# PCB_Schematic_Sheet_2.net
KiCad netlist of a schematic drawn in Altium Designer
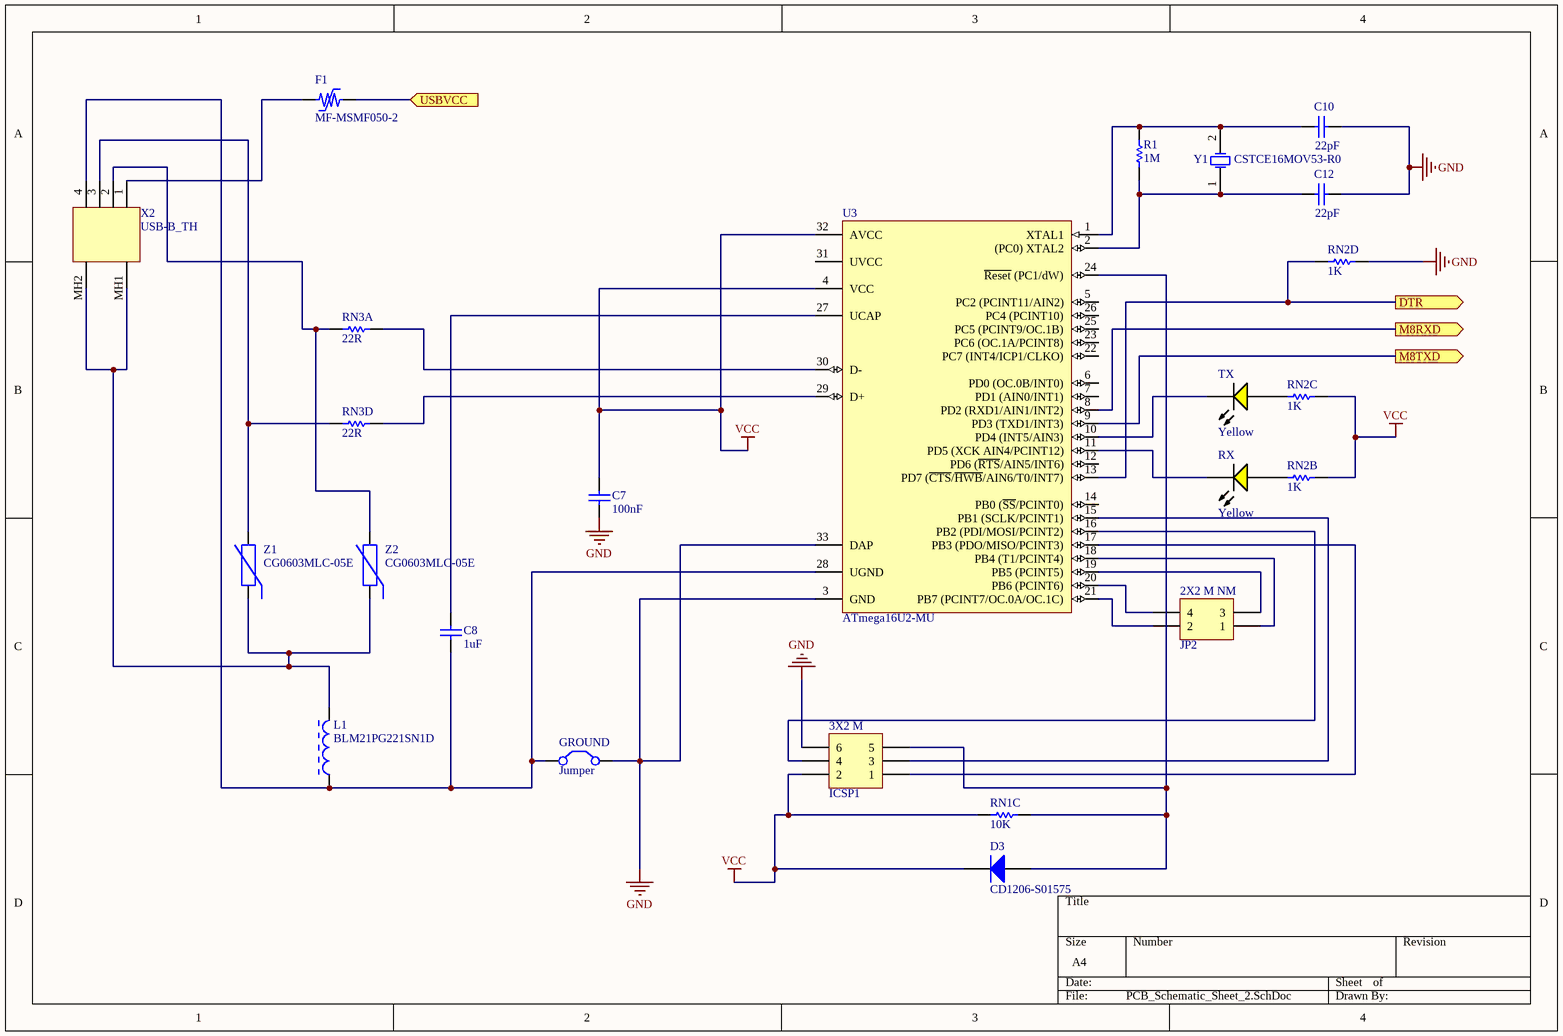
[diagram p0: PCB_Schematic_Sheet_2.SchDoc]

(export (version "E")
  (design (tool "Eeschema 10.0.6"))
  (components
    (comp (ref "2X2 M NM")
      (value "JP2")
      (footprint "HDR2X2")
      (description "Header, 2-Pin, Dual row")
      (fields (field (name "PUBLISHER") "Altium Limited"))
      (libsource (lib "Miscellaneous Connectors") (part "Header 2X2"))
    )
    (comp (ref "3X2 M")
      (value "ICSP1")
      (footprint "HDR2X3")
      (description "Header, 3-Pin, Dual row")
      (fields (field (name "PUBLISHER") "Altium Limited"))
      (libsource (lib "Miscellaneous Connectors") (part "Header 3X2"))
    )
    (comp (ref "C7")
      (value "100nF")
      (footprint "CAPC0805(2012)100_M")
      (description "CAP 100nF 50V ±10% 0805 (2012 Metric) Thickness 1mm SMD")
      (fields (field (name "TOLERANCE") "Â±10%"))
      (libsource (lib "Altium Content Vault") (part "CAP"))
    )
    (comp (ref "C8")
      (value "1uF")
      (footprint "CAPC0805(2012)145_L")
      (description "CAP 1uF 50V ±10% 0805 (2012 Metric) Thickness 1.45mm SMD")
      (fields (field (name "TOLERANCE") "Â±10%"))
      (libsource (lib "Altium Content Vault") (part "CAP"))
    )
    (comp (ref "C10")
      (value "22pF")
      (footprint "CAPC0805(2012)100_M")
      (description "CAP 22pF 50V ±5% 0805 (2012 Metric) Thickness 1mm SMD")
      (fields (field (name "TOLERANCE") "Â±5%"))
      (libsource (lib "Altium Content Vault") (part "CAP"))
    )
    (comp (ref "C12")
      (value "22pF")
      (footprint "CAPC0805(2012)100_M")
      (description "CAP 22pF 50V ±5% 0805 (2012 Metric) Thickness 1mm SMD")
      (fields (field (name "TOLERANCE") "Â±5%"))
      (libsource (lib "Altium Content Vault") (part "CAP"))
    )
    (comp (ref "D3")
      (value "CD1206-S01575")
      (footprint "BOUR-CD1206-S01575-2_L")
      (description "75 V Small Signal Switching Diode, 150 mA, 2.5 uA, 1026 Molded Package, RoHS, Tape and Reel")
      (fields (field (name "MANUFACTURER") "Bourns"))
      (libsource (lib "Altium Content Vault") (part "BOUR-A1K2-2"))
    )
    (comp (ref "F1")
      (value "MF-MSMF050-2")
      (footprint "BOUR-MF-MSMF050-2_V")
      (description "PTC Resettable Fuse, 15 V, 500 mA, -40 to 85 degC, 2-Pin SMD, RoHS, Tape and Reel")
      (fields (field (name "MANUFACTURER") "Bourns"))
      (libsource (lib "Altium Content Vault") (part "PPTC-2"))
    )
    (comp (ref "GROUND")
      (value "Jumper")
      (footprint "RAD-0.2")
      (description "Jumper Wire")
      (fields (field (name "PUBLISHER") "Altium Limited"))
      (libsource (lib "Miscellaneous Devices") (part "Jumper"))
    )
    (comp (ref "L1")
      (value "BLM21PG221SN1D")
      (footprint "MURA-BLM21-B20-CHIP-2_V2")
      (fields (field (name "MANUFACTURER") "Murata"))
      (libsource (lib "Altium Content Vault") (part "MURA-FB-2"))
    )
    (comp (ref "R1")
      (value "1M")
      (footprint "RESC0805(2012)_N")
      (description "1M 0.125W 1% 0805 (2012 Metric)  SMD")
      (fields (field (name "POWER") "0.125 W") (field (name "TOLERANCE") "1 %"))
      (libsource (lib "Altium Content Vault") (part "RES"))
    )
    (comp (ref "RN1C")
      (value "10K")
      (footprint "RESC0805(2012)_M")
      (description "10K 0.125W 1% 0805 (2012 Metric)  SMD")
      (fields (field (name "TOLERANCE") "1 %") (field (name "POWER") "0.125 W"))
      (libsource (lib "Altium Content Vault") (part "RES"))
    )
    (comp (ref "RN2B")
      (value "1K")
      (footprint "RESC0805(2012)_N")
      (description "1K 0.125W 5% 0805 (2012 Metric)  SMD")
      (fields (field (name "POWER") "0.125 W") (field (name "TOLERANCE") "5 %"))
      (libsource (lib "Altium Content Vault") (part "RES"))
    )
    (comp (ref "RN2C")
      (value "1K")
      (footprint "RESC0805(2012)_N")
      (description "1K 0.125W 5% 0805 (2012 Metric)  SMD")
      (fields (field (name "POWER") "0.125 W") (field (name "TOLERANCE") "5 %"))
      (libsource (lib "Altium Content Vault") (part "RES"))
    )
    (comp (ref "RN2D")
      (value "1K")
      (footprint "RESC0805(2012)_N")
      (description "1K 0.125W 5% 0805 (2012 Metric)  SMD")
      (fields (field (name "POWER") "0.125 W") (field (name "TOLERANCE") "5 %"))
      (libsource (lib "Altium Content Vault") (part "RES"))
    )
    (comp (ref "RN3A")
      (value "22R")
      (footprint "RESC0805(2012)_M")
      (description "22R 0.125W 5% 0805 (2012 Metric)  SMD")
      (fields (field (name "POWER") "0.125 W") (field (name "TOLERANCE") "5 %"))
      (libsource (lib "Altium Content Vault") (part "RES"))
    )
    (comp (ref "RN3D")
      (value "22R")
      (footprint "RESC0805(2012)_M")
      (description "22R 0.125W 5% 0805 (2012 Metric)  SMD")
      (fields (field (name "POWER") "0.125 W") (field (name "TOLERANCE") "5 %"))
      (libsource (lib "Altium Content Vault") (part "RES"))
    )
    (comp (ref "RX")
      (value "Yellow")
      (footprint "LTST-C190KSKT_V")
      (description "LED Uni-Color Yellow, 75 mW, 30 mA, -30 to 85 degC, 2-Pin SMD, RoHS, Tape and Reel")
      (fields (field (name "TOLERANCE") "1%"))
      (libsource (lib "Altium Content Vault") (part "LED-YELLOW-AK-2"))
    )
    (comp (ref "TX")
      (value "Yellow")
      (footprint "LTST-C190KSKT_V")
      (description "LED Uni-Color Yellow, 75 mW, 30 mA, -30 to 85 degC, 2-Pin SMD, RoHS, Tape and Reel")
      (fields (field (name "TOLERANCE") "1%"))
      (libsource (lib "Altium Content Vault") (part "LED-YELLOW-AK-2"))
    )
    (comp (ref "U3")
      (value "ATmega16U2-MU")
      (footprint "32PG_N")
      (libsource (lib "Altium Content Vault") (part "MC-8B-ATM8U2-SQ33"))
    )
    (comp (ref "X2")
      (value "USB-B_TH")
      (footprint "FCI-61729-0010BLF-6_V")
      (description "Single USB 2.0, B Type, Right Angle Jack, Through Hole, RoHS, Tube")
      (fields (field (name "MANUFACTURER") "FCI Electronics") (field (name "PARTNUMBER") "61729-0010BLF"))
      (libsource (lib "Altium Content Vault") (part "FCI-CN-1F-R6"))
    )
    (comp (ref "Y1")
      (value "CSTCE16MOV53-R0")
      (footprint "R38")
      (description "Crystal Oscillator")
      (fields (field (name "PUBLISHER") "Altium Limited"))
      (libsource (lib "Miscellaneous Devices") (part "XTAL"))
    )
    (comp (ref "Z1")
      (value "CG0603MLC-05E")
      (footprint "BOUR-CG0603-2_V")
      (description "ESD Protector, 5 V Supply, -40 to 85 degC, 1.6 x 0.8 x 0.55 mm SMD, RoHS, Tape and Reel")
      (fields (field (name "MANUFACTURER") "Bourns"))
      (libsource (lib "Altium Content Vault") (part "BOUR-VSR-2"))
    )
    (comp (ref "Z2")
      (value "CG0603MLC-05E")
      (footprint "BOUR-CG0603-2_V")
      (description "ESD Protector, 5 V Supply, -40 to 85 degC, 1.6 x 0.8 x 0.55 mm SMD, RoHS, Tape and Reel")
      (fields (field (name "MANUFACTURER") "Bourns"))
      (libsource (lib "Altium Content Vault") (part "BOUR-VSR-2"))
    )
  )
  (nets
    (net (code "1") (name "/DTR") (class "Default")
      (node (ref "RN2D") (pin "1") (pinfunction "1_1") (pintype "passive"))
      (node (ref "U3") (pin "13") (pinfunction "PD7_(~{CTS}/~{HWB}/AIN6/T0/INT7)_13") (pintype "bidirectional"))
    )
    (net (code "2") (name "/M8RXD") (class "Default")
      (node (ref "U3") (pin "8") (pinfunction "PD2_(RXD1/AIN1/INT2)_8") (pintype "bidirectional"))
    )
    (net (code "3") (name "/M8TXD") (class "Default")
      (node (ref "U3") (pin "9") (pinfunction "PD3_(TXD1/INT3)_9") (pintype "bidirectional"))
    )
    (net (code "4") (name "/USBVCC") (class "Default")
      (node (ref "F1") (pin "2") (pinfunction "2_2") (pintype "passive"))
    )
    (net (code "5") (name "GND") (class "Default")
      (node (ref "3X2 M") (pin "6") (pinfunction "6_6") (pintype "passive"))
      (node (ref "C10") (pin "2") (pinfunction "2_2") (pintype "passive"))
      (node (ref "C12") (pin "2") (pinfunction "2_2") (pintype "passive"))
      (node (ref "C7") (pin "1") (pinfunction "1_1") (pintype "passive"))
      (node (ref "GROUND") (pin "2") (pinfunction "C2_2") (pintype "passive"))
      (node (ref "RN2D") (pin "2") (pinfunction "2_2") (pintype "passive"))
      (node (ref "U3") (pin "3") (pinfunction "GND_3") (pintype "power_in"))
      (node (ref "U3") (pin "33") (pinfunction "DAP_33") (pintype "power_in"))
    )
    (net (code "6") (name "Net-(D3-A)") (class "Default")
      (node (ref "3X2 M") (pin "5") (pinfunction "5_5") (pintype "passive"))
      (node (ref "D3") (pin "1") (pinfunction "A_1") (pintype "passive"))
      (node (ref "RN1C") (pin "2") (pinfunction "2_2") (pintype "passive"))
      (node (ref "U3") (pin "24") (pinfunction "~{Reset}_(PC1/dW)_24") (pintype "bidirectional"))
    )
    (net (code "7") (name "Net-(F1-Pad1)") (class "Default")
      (node (ref "F1") (pin "1") (pinfunction "1_1") (pintype "passive"))
      (node (ref "X2") (pin "1") (pinfunction "1_1") (pintype "passive"))
    )
    (net (code "8") (name "Net-(GROUND-C1)") (class "Default")
      (node (ref "C8") (pin "1") (pinfunction "1_1") (pintype "passive"))
      (node (ref "GROUND") (pin "1") (pinfunction "C1_1") (pintype "passive"))
      (node (ref "L1") (pin "1") (pinfunction "1_1") (pintype "passive"))
      (node (ref "U3") (pin "28") (pinfunction "UGND_28") (pintype "power_in"))
      (node (ref "X2") (pin "4") (pinfunction "4_4") (pintype "passive"))
    )
    (net (code "9") (name "Net-(L1-Pad2)") (class "Default")
      (node (ref "L1") (pin "2") (pinfunction "2_2") (pintype "passive"))
      (node (ref "X2") (pin "MH1") (pinfunction "MH1_MH1") (pintype "passive"))
      (node (ref "X2") (pin "MH2") (pinfunction "MH2_MH2") (pintype "passive"))
      (node (ref "Z1") (pin "1") (pinfunction "1_1") (pintype "passive"))
      (node (ref "Z2") (pin "1") (pinfunction "1_1") (pintype "passive"))
    )
    (net (code "10") (name "Net-(RN3A-Pad1)") (class "Default")
      (node (ref "RN3A") (pin "1") (pinfunction "1_1") (pintype "passive"))
      (node (ref "X2") (pin "2") (pinfunction "2_2") (pintype "passive"))
      (node (ref "Z2") (pin "2") (pinfunction "2_2") (pintype "passive"))
    )
    (net (code "11") (name "Net-(RN3D-Pad1)") (class "Default")
      (node (ref "RN3D") (pin "1") (pinfunction "1_1") (pintype "passive"))
      (node (ref "X2") (pin "3") (pinfunction "3_3") (pintype "passive"))
      (node (ref "Z1") (pin "2") (pinfunction "2_2") (pintype "passive"))
    )
    (net (code "12") (name "Net-(RX-A)") (class "Default")
      (node (ref "RN2B") (pin "1") (pinfunction "1_1") (pintype "passive"))
      (node (ref "RX") (pin "1") (pinfunction "A_1") (pintype "passive"))
    )
    (net (code "13") (name "Net-(RX-K)") (class "Default")
      (node (ref "RX") (pin "2") (pinfunction "K_2") (pintype "passive"))
      (node (ref "U3") (pin "11") (pinfunction "PD5_(XCK_AIN4/PCINT12)_11") (pintype "bidirectional"))
    )
    (net (code "14") (name "Net-(TX-A)") (class "Default")
      (node (ref "RN2C") (pin "1") (pinfunction "1_1") (pintype "passive"))
      (node (ref "TX") (pin "1") (pinfunction "A_1") (pintype "passive"))
    )
    (net (code "15") (name "Net-(TX-K)") (class "Default")
      (node (ref "TX") (pin "2") (pinfunction "K_2") (pintype "passive"))
      (node (ref "U3") (pin "10") (pinfunction "PD4_(INT5/AIN3)_10") (pintype "bidirectional"))
    )
    (net (code "16") (name "Net-(U3-(PC0)_XTAL2)") (class "Default")
      (node (ref "C12") (pin "1") (pinfunction "1_1") (pintype "passive"))
      (node (ref "R1") (pin "1") (pinfunction "1_1") (pintype "passive"))
      (node (ref "U3") (pin "2") (pinfunction "(PC0)_XTAL2_2") (pintype "bidirectional"))
      (node (ref "Y1") (pin "1") (pinfunction "OSC1_1") (pintype "passive"))
    )
    (net (code "17") (name "Net-(U3-D+)") (class "Default")
      (node (ref "RN3D") (pin "2") (pinfunction "2_2") (pintype "passive"))
      (node (ref "U3") (pin "29") (pinfunction "D+_29") (pintype "bidirectional"))
    )
    (net (code "18") (name "Net-(U3-D-)") (class "Default")
      (node (ref "RN3A") (pin "2") (pinfunction "2_2") (pintype "passive"))
      (node (ref "U3") (pin "30") (pinfunction "D-_30") (pintype "bidirectional"))
    )
    (net (code "19") (name "Net-(U3-PB1_(SCLK{slash}PCINT1))") (class "Default")
      (node (ref "3X2 M") (pin "3") (pinfunction "3_3") (pintype "passive"))
      (node (ref "U3") (pin "15") (pinfunction "PB1_(SCLK/PCINT1)_15") (pintype "bidirectional"))
    )
    (net (code "20") (name "Net-(U3-PB2_(PDI{slash}MOSI{slash}PCINT2))") (class "Default")
      (node (ref "3X2 M") (pin "4") (pinfunction "4_4") (pintype "passive"))
      (node (ref "U3") (pin "16") (pinfunction "PB2_(PDI/MOSI/PCINT2)_16") (pintype "bidirectional"))
    )
    (net (code "21") (name "Net-(U3-PB3_(PDO{slash}MISO{slash}PCINT3))") (class "Default")
      (node (ref "3X2 M") (pin "1") (pinfunction "1_1") (pintype "passive"))
      (node (ref "U3") (pin "17") (pinfunction "PB3_(PDO/MISO/PCINT3)_17") (pintype "bidirectional"))
    )
    (net (code "22") (name "Net-(U3-PB4_(T1{slash}PCINT4))") (class "Default")
      (node (ref "2X2 M NM") (pin "1") (pinfunction "1_1") (pintype "passive"))
      (node (ref "U3") (pin "18") (pinfunction "PB4_(T1/PCINT4)_18") (pintype "bidirectional"))
    )
    (net (code "23") (name "Net-(U3-PB5_(PCINT5))") (class "Default")
      (node (ref "2X2 M NM") (pin "3") (pinfunction "3_3") (pintype "passive"))
      (node (ref "U3") (pin "19") (pinfunction "PB5_(PCINT5)_19") (pintype "bidirectional"))
    )
    (net (code "24") (name "Net-(U3-PB6_(PCINT6))") (class "Default")
      (node (ref "2X2 M NM") (pin "4") (pinfunction "4_4") (pintype "passive"))
      (node (ref "U3") (pin "20") (pinfunction "PB6_(PCINT6)_20") (pintype "bidirectional"))
    )
    (net (code "25") (name "Net-(U3-PB7_(PCINT7{slash}OC.0A{slash}OC.1C))") (class "Default")
      (node (ref "2X2 M NM") (pin "2") (pinfunction "2_2") (pintype "passive"))
      (node (ref "U3") (pin "21") (pinfunction "PB7_(PCINT7/OC.0A/OC.1C)_21") (pintype "bidirectional"))
    )
    (net (code "26") (name "Net-(U3-UCAP)") (class "Default")
      (node (ref "C8") (pin "2") (pinfunction "2_2") (pintype "passive"))
      (node (ref "U3") (pin "27") (pinfunction "UCAP_27") (pintype "power_in"))
    )
    (net (code "27") (name "Net-(U3-XTAL1)") (class "Default")
      (node (ref "C10") (pin "1") (pinfunction "1_1") (pintype "passive"))
      (node (ref "R1") (pin "2") (pinfunction "2_2") (pintype "passive"))
      (node (ref "U3") (pin "1") (pinfunction "XTAL1_1") (pintype "input"))
      (node (ref "Y1") (pin "2") (pinfunction "OSC2_2") (pintype "passive"))
    )
    (net (code "28") (name "VCC") (class "Default")
      (node (ref "3X2 M") (pin "2") (pinfunction "2_2") (pintype "passive"))
      (node (ref "C7") (pin "2") (pinfunction "2_2") (pintype "passive"))
      (node (ref "D3") (pin "2") (pinfunction "K_2") (pintype "passive"))
      (node (ref "RN1C") (pin "1") (pinfunction "1_1") (pintype "passive"))
      (node (ref "RN2B") (pin "2") (pinfunction "2_2") (pintype "passive"))
      (node (ref "RN2C") (pin "2") (pinfunction "2_2") (pintype "passive"))
      (node (ref "U3") (pin "32") (pinfunction "AVCC_32") (pintype "power_in"))
      (node (ref "U3") (pin "4") (pinfunction "VCC_4") (pintype "power_in"))
    )
    (net (code "29") (name "unconnected-(U3-PB0_(~{SS}{slash}PCINT0)-Pad14)") (class "Default")
      (node (ref "U3") (pin "14") (pinfunction "PB0_(~{SS}/PCINT0)_14") (pintype "bidirectional"))
    )
    (net (code "30") (name "unconnected-(U3-PC2_(PCINT11{slash}AIN2)-Pad5)") (class "Default")
      (node (ref "U3") (pin "5") (pinfunction "PC2_(PCINT11/AIN2)_5") (pintype "bidirectional"))
    )
    (net (code "31") (name "unconnected-(U3-PC4_(PCINT10)-Pad26)") (class "Default")
      (node (ref "U3") (pin "26") (pinfunction "PC4_(PCINT10)_26") (pintype "bidirectional"))
    )
    (net (code "32") (name "unconnected-(U3-PC5_(PCINT9{slash}OC.1B)-Pad25)") (class "Default")
      (node (ref "U3") (pin "25") (pinfunction "PC5_(PCINT9/OC.1B)_25") (pintype "bidirectional"))
    )
    (net (code "33") (name "unconnected-(U3-PC6_(OC.1A{slash}PCINT8)-Pad23)") (class "Default")
      (node (ref "U3") (pin "23") (pinfunction "PC6_(OC.1A/PCINT8)_23") (pintype "bidirectional"))
    )
    (net (code "34") (name "unconnected-(U3-PC7_(INT4{slash}ICP1{slash}CLKO)-Pad22)") (class "Default")
      (node (ref "U3") (pin "22") (pinfunction "PC7_(INT4/ICP1/CLKO)_22") (pintype "bidirectional"))
    )
    (net (code "35") (name "unconnected-(U3-PD0_(OC.0B{slash}INT0)-Pad6)") (class "Default")
      (node (ref "U3") (pin "6") (pinfunction "PD0_(OC.0B/INT0)_6") (pintype "bidirectional"))
    )
    (net (code "36") (name "unconnected-(U3-PD1_(AIN0{slash}INT1)-Pad7)") (class "Default")
      (node (ref "U3") (pin "7") (pinfunction "PD1_(AIN0/INT1)_7") (pintype "bidirectional"))
    )
    (net (code "37") (name "unconnected-(U3-PD6_(~{RTS}{slash}AIN5{slash}INT6)-Pad12)") (class "Default")
      (node (ref "U3") (pin "12") (pinfunction "PD6_(~{RTS}/AIN5/INT6)_12") (pintype "bidirectional"))
    )
    (net (code "38") (name "unconnected-(U3-UVCC-Pad31)") (class "Default")
      (node (ref "U3") (pin "31") (pinfunction "UVCC_31") (pintype "power_in"))
    )
  )
)
